# tlc5940_1.net
KiCad netlist of a schematic drawn in EAGLE
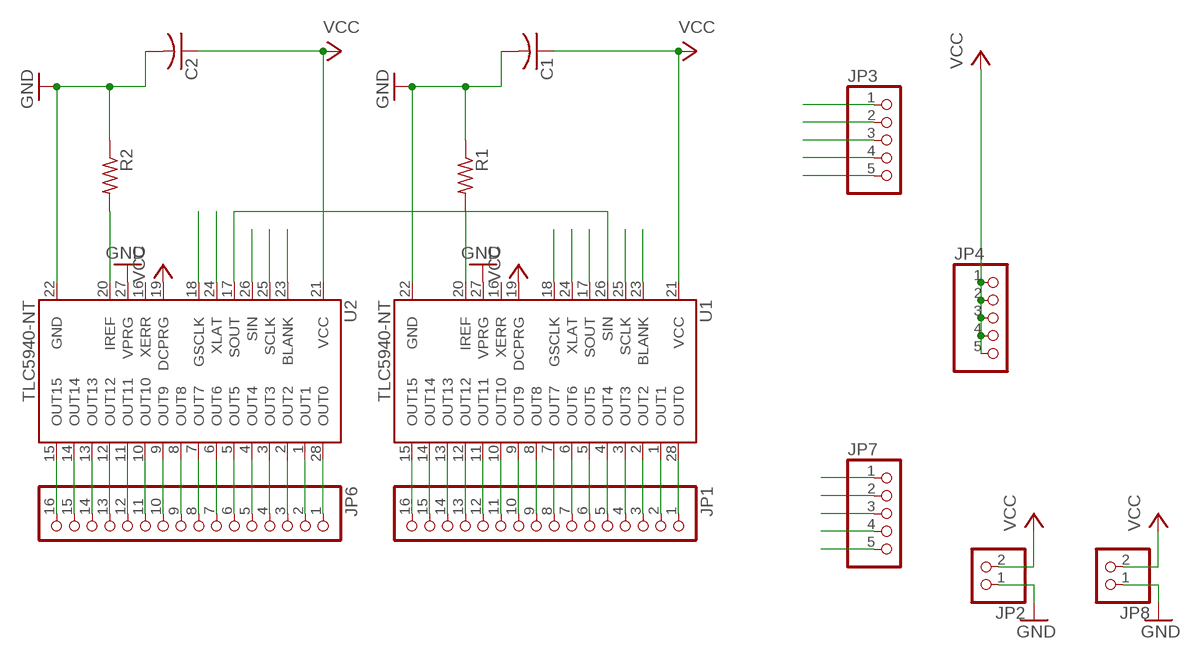
[diagram p0: schematic, sheet 1]

(export (version "E")
  (design (tool "Eeschema 10.0.6"))
  (components
    (comp (ref "C1")
      (value "C-US025-024X044")
      (footprint "eagle-import:C025-024X044")
      (libsource (lib "eagle-import") (part "C-US025-024X044"))
    )
    (comp (ref "C2")
      (value "C-US025-024X044")
      (footprint "eagle-import:C025-024X044")
      (libsource (lib "eagle-import") (part "C-US025-024X044"))
    )
    (comp (ref "JP1")
      (value "PINHD-1X16")
      (footprint "eagle-import:1X16")
      (libsource (lib "eagle-import") (part "PINHD-1X16"))
    )
    (comp (ref "JP2")
      (value "PINHD-1X2")
      (footprint "eagle-import:1X02")
      (libsource (lib "eagle-import") (part "PINHD-1X2"))
    )
    (comp (ref "JP3")
      (value "PINHD-1X5")
      (footprint "eagle-import:1X05")
      (libsource (lib "eagle-import") (part "PINHD-1X5"))
    )
    (comp (ref "JP4")
      (value "PINHD-1X5")
      (footprint "eagle-import:1X05")
      (libsource (lib "eagle-import") (part "PINHD-1X5"))
    )
    (comp (ref "JP6")
      (value "PINHD-1X16")
      (footprint "eagle-import:1X16")
      (libsource (lib "eagle-import") (part "PINHD-1X16"))
    )
    (comp (ref "JP7")
      (value "PINHD-1X5")
      (footprint "eagle-import:1X05")
      (libsource (lib "eagle-import") (part "PINHD-1X5"))
    )
    (comp (ref "JP8")
      (value "PINHD-1X2")
      (footprint "eagle-import:1X02")
      (libsource (lib "eagle-import") (part "PINHD-1X2"))
    )
    (comp (ref "R1")
      (value "R-US_0613/5V")
      (footprint "eagle-import:P0613V")
      (libsource (lib "eagle-import") (part "R-US_0613/5V"))
    )
    (comp (ref "R2")
      (value "R-US_0613/5V")
      (footprint "eagle-import:P0613V")
      (libsource (lib "eagle-import") (part "R-US_0613/5V"))
    )
    (comp (ref "U1")
      (value "TLC5940-NT")
      (footprint "eagle-import:DIL28-3")
      (libsource (lib "eagle-import") (part "TLC5940-NT"))
    )
    (comp (ref "U2")
      (value "TLC5940-NT")
      (footprint "eagle-import:DIL28-3")
      (libsource (lib "eagle-import") (part "TLC5940-NT"))
    )
  )
  (nets
    (net (code "1") (name "/BLANK") (class "Default")
      (node (ref "JP3") (pin "5") (pinfunction "5_5") (pintype "passive"))
      (node (ref "JP7") (pin "5") (pinfunction "5_5") (pintype "passive"))
      (node (ref "U1") (pin "23") (pinfunction "BLANK_23") (pintype "bidirectional"))
      (node (ref "U2") (pin "23") (pinfunction "BLANK_23") (pintype "bidirectional"))
    )
    (net (code "2") (name "/GSCLK") (class "Default")
      (node (ref "JP3") (pin "1") (pinfunction "1_1") (pintype "passive"))
      (node (ref "JP7") (pin "1") (pinfunction "1_1") (pintype "passive"))
      (node (ref "U1") (pin "18") (pinfunction "GSCLK_18") (pintype "bidirectional"))
      (node (ref "U2") (pin "18") (pinfunction "GSCLK_18") (pintype "bidirectional"))
    )
    (net (code "3") (name "/SCLK") (class "Default")
      (node (ref "JP3") (pin "4") (pinfunction "4_4") (pintype "passive"))
      (node (ref "JP7") (pin "4") (pinfunction "4_4") (pintype "passive"))
      (node (ref "U1") (pin "25") (pinfunction "SCLK_25") (pintype "bidirectional"))
      (node (ref "U2") (pin "25") (pinfunction "SCLK_25") (pintype "bidirectional"))
    )
    (net (code "4") (name "/SIN") (class "Default")
      (node (ref "JP3") (pin "3") (pinfunction "3_3") (pintype "passive"))
      (node (ref "U2") (pin "26") (pinfunction "SIN_26") (pintype "bidirectional"))
    )
    (net (code "5") (name "/SOUT") (class "Default")
      (node (ref "JP7") (pin "3") (pinfunction "3_3") (pintype "passive"))
      (node (ref "U1") (pin "17") (pinfunction "SOUT_17") (pintype "bidirectional"))
    )
    (net (code "6") (name "/XLAT") (class "Default")
      (node (ref "JP3") (pin "2") (pinfunction "2_2") (pintype "passive"))
      (node (ref "JP7") (pin "2") (pinfunction "2_2") (pintype "passive"))
      (node (ref "U1") (pin "24") (pinfunction "XLAT_24") (pintype "bidirectional"))
      (node (ref "U2") (pin "24") (pinfunction "XLAT_24") (pintype "bidirectional"))
    )
    (net (code "7") (name "GND") (class "Default")
      (node (ref "C1") (pin "2") (pinfunction "2_2") (pintype "passive"))
      (node (ref "C2") (pin "2") (pinfunction "2_2") (pintype "passive"))
      (node (ref "JP2") (pin "1") (pinfunction "1_1") (pintype "passive"))
      (node (ref "JP8") (pin "1") (pinfunction "1_1") (pintype "passive"))
      (node (ref "R1") (pin "1") (pinfunction "1_1") (pintype "passive"))
      (node (ref "R2") (pin "1") (pinfunction "1_1") (pintype "passive"))
      (node (ref "U1") (pin "22") (pinfunction "GND_22") (pintype "bidirectional"))
      (node (ref "U1") (pin "27") (pinfunction "VPRG_27") (pintype "bidirectional"))
      (node (ref "U2") (pin "22") (pinfunction "GND_22") (pintype "bidirectional"))
      (node (ref "U2") (pin "27") (pinfunction "VPRG_27") (pintype "bidirectional"))
    )
    (net (code "8") (name "Net-(U1-IREF)") (class "Default")
      (node (ref "R1") (pin "2") (pinfunction "2_2") (pintype "passive"))
      (node (ref "U1") (pin "20") (pinfunction "IREF_20") (pintype "bidirectional"))
    )
    (net (code "9") (name "Net-(U1-OUT0)") (class "Default")
      (node (ref "JP1") (pin "1") (pinfunction "1_1") (pintype "passive"))
      (node (ref "U1") (pin "28") (pinfunction "OUT0_28") (pintype "bidirectional"))
    )
    (net (code "10") (name "Net-(U1-OUT1)") (class "Default")
      (node (ref "JP1") (pin "2") (pinfunction "2_2") (pintype "passive"))
      (node (ref "U1") (pin "1") (pinfunction "OUT1_1") (pintype "bidirectional"))
    )
    (net (code "11") (name "Net-(U1-OUT2)") (class "Default")
      (node (ref "JP1") (pin "3") (pinfunction "3_3") (pintype "passive"))
      (node (ref "U1") (pin "2") (pinfunction "OUT2_2") (pintype "bidirectional"))
    )
    (net (code "12") (name "Net-(U1-OUT3)") (class "Default")
      (node (ref "JP1") (pin "4") (pinfunction "4_4") (pintype "passive"))
      (node (ref "U1") (pin "3") (pinfunction "OUT3_3") (pintype "bidirectional"))
    )
    (net (code "13") (name "Net-(U1-OUT4)") (class "Default")
      (node (ref "JP1") (pin "5") (pinfunction "5_5") (pintype "passive"))
      (node (ref "U1") (pin "4") (pinfunction "OUT4_4") (pintype "bidirectional"))
    )
    (net (code "14") (name "Net-(U1-OUT5)") (class "Default")
      (node (ref "JP1") (pin "6") (pinfunction "6_6") (pintype "passive"))
      (node (ref "U1") (pin "5") (pinfunction "OUT5_5") (pintype "bidirectional"))
    )
    (net (code "15") (name "Net-(U1-OUT6)") (class "Default")
      (node (ref "JP1") (pin "7") (pinfunction "7_7") (pintype "passive"))
      (node (ref "U1") (pin "6") (pinfunction "OUT6_6") (pintype "bidirectional"))
    )
    (net (code "16") (name "Net-(U1-OUT7)") (class "Default")
      (node (ref "JP1") (pin "8") (pinfunction "8_8") (pintype "passive"))
      (node (ref "U1") (pin "7") (pinfunction "OUT7_7") (pintype "bidirectional"))
    )
    (net (code "17") (name "Net-(U1-OUT8)") (class "Default")
      (node (ref "JP1") (pin "9") (pinfunction "9_9") (pintype "passive"))
      (node (ref "U1") (pin "8") (pinfunction "OUT8_8") (pintype "bidirectional"))
    )
    (net (code "18") (name "Net-(U1-OUT9)") (class "Default")
      (node (ref "JP1") (pin "10") (pinfunction "10_10") (pintype "passive"))
      (node (ref "U1") (pin "9") (pinfunction "OUT9_9") (pintype "bidirectional"))
    )
    (net (code "19") (name "Net-(U1-OUT10)") (class "Default")
      (node (ref "JP1") (pin "11") (pinfunction "11_11") (pintype "passive"))
      (node (ref "U1") (pin "10") (pinfunction "OUT10_10") (pintype "bidirectional"))
    )
    (net (code "20") (name "Net-(U1-OUT11)") (class "Default")
      (node (ref "JP1") (pin "12") (pinfunction "12_12") (pintype "passive"))
      (node (ref "U1") (pin "11") (pinfunction "OUT11_11") (pintype "bidirectional"))
    )
    (net (code "21") (name "Net-(U1-OUT12)") (class "Default")
      (node (ref "JP1") (pin "13") (pinfunction "13_13") (pintype "passive"))
      (node (ref "U1") (pin "12") (pinfunction "OUT12_12") (pintype "bidirectional"))
    )
    (net (code "22") (name "Net-(U1-OUT13)") (class "Default")
      (node (ref "JP1") (pin "14") (pinfunction "14_14") (pintype "passive"))
      (node (ref "U1") (pin "13") (pinfunction "OUT13_13") (pintype "bidirectional"))
    )
    (net (code "23") (name "Net-(U1-OUT14)") (class "Default")
      (node (ref "JP1") (pin "15") (pinfunction "15_15") (pintype "passive"))
      (node (ref "U1") (pin "14") (pinfunction "OUT14_14") (pintype "bidirectional"))
    )
    (net (code "24") (name "Net-(U1-OUT15)") (class "Default")
      (node (ref "JP1") (pin "16") (pinfunction "16_16") (pintype "passive"))
      (node (ref "U1") (pin "15") (pinfunction "OUT15_15") (pintype "bidirectional"))
    )
    (net (code "25") (name "Net-(U1-SIN)") (class "Default")
      (node (ref "U1") (pin "26") (pinfunction "SIN_26") (pintype "bidirectional"))
      (node (ref "U2") (pin "17") (pinfunction "SOUT_17") (pintype "bidirectional"))
    )
    (net (code "26") (name "Net-(U2-IREF)") (class "Default")
      (node (ref "R2") (pin "2") (pinfunction "2_2") (pintype "passive"))
      (node (ref "U2") (pin "20") (pinfunction "IREF_20") (pintype "bidirectional"))
    )
    (net (code "27") (name "Net-(U2-OUT0)") (class "Default")
      (node (ref "JP6") (pin "1") (pinfunction "1_1") (pintype "passive"))
      (node (ref "U2") (pin "28") (pinfunction "OUT0_28") (pintype "bidirectional"))
    )
    (net (code "28") (name "Net-(U2-OUT1)") (class "Default")
      (node (ref "JP6") (pin "2") (pinfunction "2_2") (pintype "passive"))
      (node (ref "U2") (pin "1") (pinfunction "OUT1_1") (pintype "bidirectional"))
    )
    (net (code "29") (name "Net-(U2-OUT2)") (class "Default")
      (node (ref "JP6") (pin "3") (pinfunction "3_3") (pintype "passive"))
      (node (ref "U2") (pin "2") (pinfunction "OUT2_2") (pintype "bidirectional"))
    )
    (net (code "30") (name "Net-(U2-OUT3)") (class "Default")
      (node (ref "JP6") (pin "4") (pinfunction "4_4") (pintype "passive"))
      (node (ref "U2") (pin "3") (pinfunction "OUT3_3") (pintype "bidirectional"))
    )
    (net (code "31") (name "Net-(U2-OUT4)") (class "Default")
      (node (ref "JP6") (pin "5") (pinfunction "5_5") (pintype "passive"))
      (node (ref "U2") (pin "4") (pinfunction "OUT4_4") (pintype "bidirectional"))
    )
    (net (code "32") (name "Net-(U2-OUT5)") (class "Default")
      (node (ref "JP6") (pin "6") (pinfunction "6_6") (pintype "passive"))
      (node (ref "U2") (pin "5") (pinfunction "OUT5_5") (pintype "bidirectional"))
    )
    (net (code "33") (name "Net-(U2-OUT6)") (class "Default")
      (node (ref "JP6") (pin "7") (pinfunction "7_7") (pintype "passive"))
      (node (ref "U2") (pin "6") (pinfunction "OUT6_6") (pintype "bidirectional"))
    )
    (net (code "34") (name "Net-(U2-OUT7)") (class "Default")
      (node (ref "JP6") (pin "8") (pinfunction "8_8") (pintype "passive"))
      (node (ref "U2") (pin "7") (pinfunction "OUT7_7") (pintype "bidirectional"))
    )
    (net (code "35") (name "Net-(U2-OUT8)") (class "Default")
      (node (ref "JP6") (pin "9") (pinfunction "9_9") (pintype "passive"))
      (node (ref "U2") (pin "8") (pinfunction "OUT8_8") (pintype "bidirectional"))
    )
    (net (code "36") (name "Net-(U2-OUT9)") (class "Default")
      (node (ref "JP6") (pin "10") (pinfunction "10_10") (pintype "passive"))
      (node (ref "U2") (pin "9") (pinfunction "OUT9_9") (pintype "bidirectional"))
    )
    (net (code "37") (name "Net-(U2-OUT10)") (class "Default")
      (node (ref "JP6") (pin "11") (pinfunction "11_11") (pintype "passive"))
      (node (ref "U2") (pin "10") (pinfunction "OUT10_10") (pintype "bidirectional"))
    )
    (net (code "38") (name "Net-(U2-OUT11)") (class "Default")
      (node (ref "JP6") (pin "12") (pinfunction "12_12") (pintype "passive"))
      (node (ref "U2") (pin "11") (pinfunction "OUT11_11") (pintype "bidirectional"))
    )
    (net (code "39") (name "Net-(U2-OUT12)") (class "Default")
      (node (ref "JP6") (pin "13") (pinfunction "13_13") (pintype "passive"))
      (node (ref "U2") (pin "12") (pinfunction "OUT12_12") (pintype "bidirectional"))
    )
    (net (code "40") (name "Net-(U2-OUT13)") (class "Default")
      (node (ref "JP6") (pin "14") (pinfunction "14_14") (pintype "passive"))
      (node (ref "U2") (pin "13") (pinfunction "OUT13_13") (pintype "bidirectional"))
    )
    (net (code "41") (name "Net-(U2-OUT14)") (class "Default")
      (node (ref "JP6") (pin "15") (pinfunction "15_15") (pintype "passive"))
      (node (ref "U2") (pin "14") (pinfunction "OUT14_14") (pintype "bidirectional"))
    )
    (net (code "42") (name "Net-(U2-OUT15)") (class "Default")
      (node (ref "JP6") (pin "16") (pinfunction "16_16") (pintype "passive"))
      (node (ref "U2") (pin "15") (pinfunction "OUT15_15") (pintype "bidirectional"))
    )
    (net (code "43") (name "VCC") (class "Default")
      (node (ref "C1") (pin "1") (pinfunction "1_1") (pintype "passive"))
      (node (ref "C2") (pin "1") (pinfunction "1_1") (pintype "passive"))
      (node (ref "JP2") (pin "2") (pinfunction "2_2") (pintype "passive"))
      (node (ref "JP4") (pin "1") (pinfunction "1_1") (pintype "passive"))
      (node (ref "JP4") (pin "2") (pinfunction "2_2") (pintype "passive"))
      (node (ref "JP4") (pin "3") (pinfunction "3_3") (pintype "passive"))
      (node (ref "JP4") (pin "4") (pinfunction "4_4") (pintype "passive"))
      (node (ref "JP4") (pin "5") (pinfunction "5_5") (pintype "passive"))
      (node (ref "JP8") (pin "2") (pinfunction "2_2") (pintype "passive"))
      (node (ref "U1") (pin "19") (pinfunction "DCPRG_19") (pintype "bidirectional"))
      (node (ref "U1") (pin "21") (pinfunction "VCC_21") (pintype "bidirectional"))
      (node (ref "U2") (pin "19") (pinfunction "DCPRG_19") (pintype "bidirectional"))
      (node (ref "U2") (pin "21") (pinfunction "VCC_21") (pintype "bidirectional"))
    )
    (net (code "44") (name "unconnected-(U1-XERR-Pad16)") (class "Default")
      (node (ref "U1") (pin "16") (pinfunction "XERR_16") (pintype "bidirectional"))
    )
    (net (code "45") (name "unconnected-(U2-XERR-Pad16)") (class "Default")
      (node (ref "U2") (pin "16") (pinfunction "XERR_16") (pintype "bidirectional"))
    )
  )
)
